# Main_8.net
KiCad netlist of a schematic drawn in Altium Designer
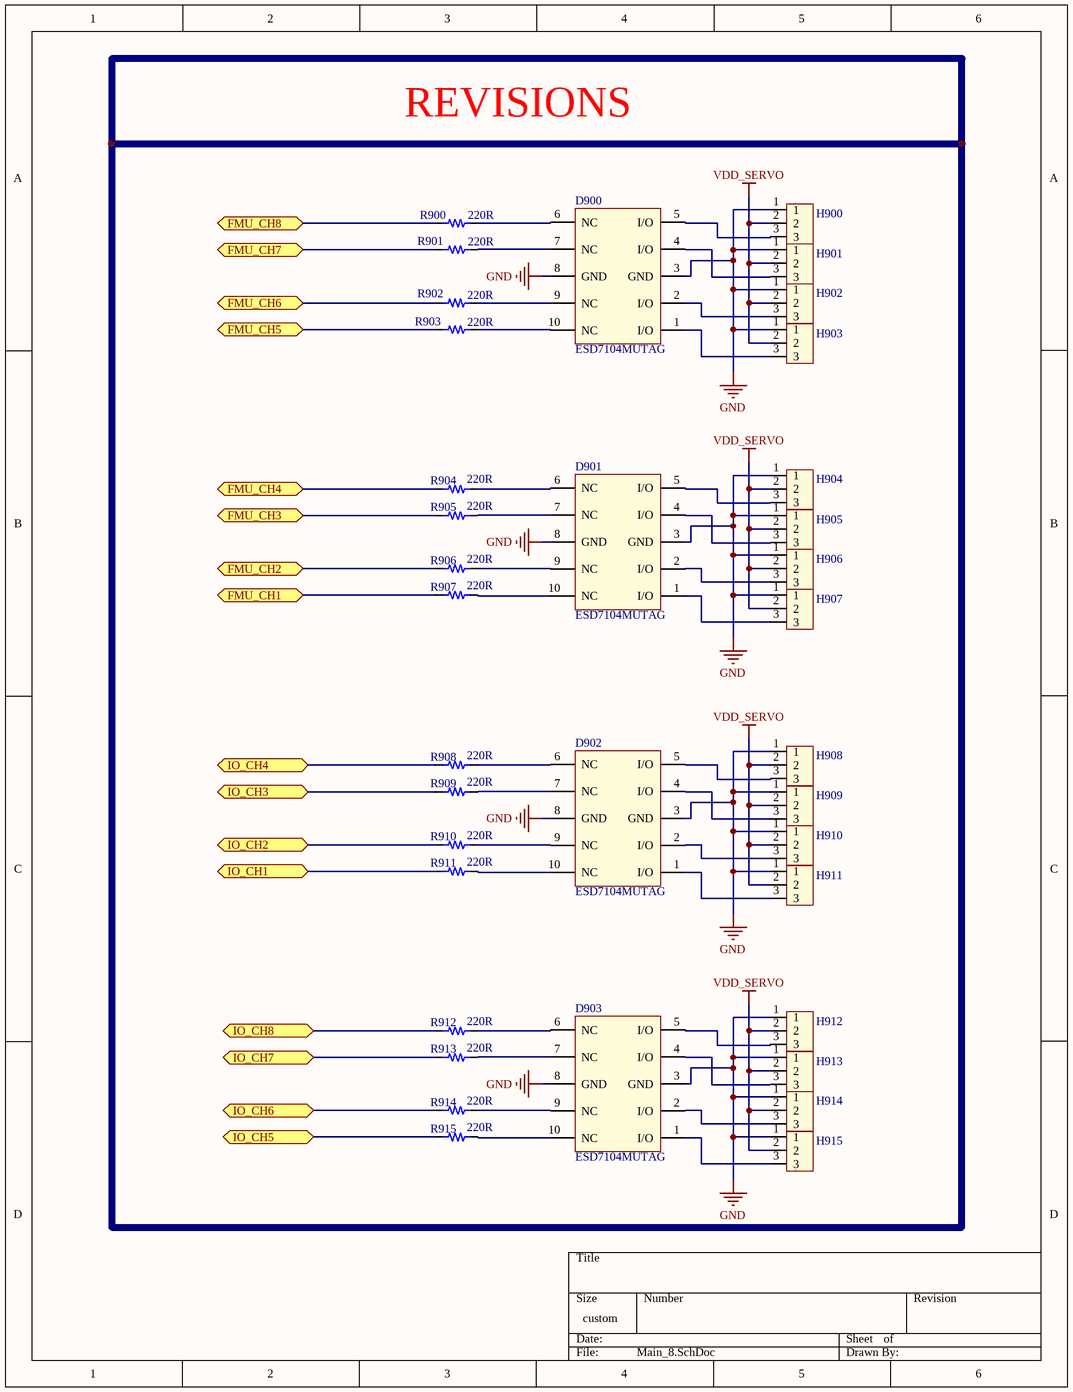
[diagram p0: Main_8.SchDoc]

(export (version "E")
  (design (tool "Eeschema 10.0.6"))
  (components
    (comp (ref "D900")
      (value "ESD7104MUTAG")
      (footprint "UDFN10 2.5x1, 0.5P")
      (description "TVS DIODE 5VWM 10VC 10UDFN")
      (libsource (lib "UAV_mainboard") (part "ESD7104MUTAG"))
    )
    (comp (ref "D901")
      (value "ESD7104MUTAG")
      (footprint "UDFN10 2.5x1, 0.5P")
      (description "TVS DIODE 5VWM 10VC 10UDFN")
      (libsource (lib "UAV_mainboard") (part "ESD7104MUTAG"))
    )
    (comp (ref "D902")
      (value "ESD7104MUTAG")
      (footprint "UDFN10 2.5x1, 0.5P")
      (description "TVS DIODE 5VWM 10VC 10UDFN")
      (libsource (lib "UAV_mainboard") (part "ESD7104MUTAG"))
    )
    (comp (ref "D903")
      (value "ESD7104MUTAG")
      (footprint "UDFN10 2.5x1, 0.5P")
      (description "TVS DIODE 5VWM 10VC 10UDFN")
      (libsource (lib "UAV_mainboard") (part "ESD7104MUTAG"))
    )
    (comp (ref "H900")
      (value "Header 3x1")
      (footprint "Header 3x1")
      (libsource (lib "UAV_mainboard") (part "Header 3x1"))
    )
    (comp (ref "H901")
      (value "Header 3x1")
      (footprint "Header 3x1")
      (libsource (lib "UAV_mainboard") (part "Header 3x1"))
    )
    (comp (ref "H902")
      (value "Header 3x1")
      (footprint "Header 3x1")
      (libsource (lib "UAV_mainboard") (part "Header 3x1"))
    )
    (comp (ref "H903")
      (value "Header 3x1")
      (footprint "Header 3x1")
      (libsource (lib "UAV_mainboard") (part "Header 3x1"))
    )
    (comp (ref "H904")
      (value "Header 3x1")
      (footprint "Header 3x1")
      (libsource (lib "UAV_mainboard") (part "Header 3x1"))
    )
    (comp (ref "H905")
      (value "Header 3x1")
      (footprint "Header 3x1")
      (libsource (lib "UAV_mainboard") (part "Header 3x1"))
    )
    (comp (ref "H906")
      (value "Header 3x1")
      (footprint "Header 3x1")
      (libsource (lib "UAV_mainboard") (part "Header 3x1"))
    )
    (comp (ref "H907")
      (value "Header 3x1")
      (footprint "Header 3x1")
      (libsource (lib "UAV_mainboard") (part "Header 3x1"))
    )
    (comp (ref "H908")
      (value "Header 3x1")
      (footprint "Header 3x1")
      (libsource (lib "UAV_mainboard") (part "Header 3x1"))
    )
    (comp (ref "H909")
      (value "Header 3x1")
      (footprint "Header 3x1")
      (libsource (lib "UAV_mainboard") (part "Header 3x1"))
    )
    (comp (ref "H910")
      (value "Header 3x1")
      (footprint "Header 3x1")
      (libsource (lib "UAV_mainboard") (part "Header 3x1"))
    )
    (comp (ref "H911")
      (value "Header 3x1")
      (footprint "Header 3x1")
      (libsource (lib "UAV_mainboard") (part "Header 3x1"))
    )
    (comp (ref "H912")
      (value "Header 3x1")
      (footprint "Header 3x1")
      (libsource (lib "UAV_mainboard") (part "Header 3x1"))
    )
    (comp (ref "H913")
      (value "Header 3x1")
      (footprint "Header 3x1")
      (libsource (lib "UAV_mainboard") (part "Header 3x1"))
    )
    (comp (ref "H914")
      (value "Header 3x1")
      (footprint "Header 3x1")
      (libsource (lib "UAV_mainboard") (part "Header 3x1"))
    )
    (comp (ref "H915")
      (value "Header 3x1")
      (footprint "Header 3x1")
      (libsource (lib "UAV_mainboard") (part "Header 3x1"))
    )
    (comp (ref "R900")
      (value "220R")
      (footprint "R0402")
      (description "RES 220 OHM 1% 1/16W 0402")
      (libsource (lib "UAV_mainboard") (part "RC0402FR-07220RL"))
    )
    (comp (ref "R901")
      (value "220R")
      (footprint "R0402")
      (description "RES 220 OHM 1% 1/16W 0402")
      (libsource (lib "UAV_mainboard") (part "RC0402FR-07220RL"))
    )
    (comp (ref "R902")
      (value "220R")
      (footprint "R0402")
      (description "RES 220 OHM 1% 1/16W 0402")
      (libsource (lib "UAV_mainboard") (part "RC0402FR-07220RL"))
    )
    (comp (ref "R903")
      (value "220R")
      (footprint "R0402")
      (description "RES 220 OHM 1% 1/16W 0402")
      (libsource (lib "UAV_mainboard") (part "RC0402FR-07220RL"))
    )
    (comp (ref "R904")
      (value "220R")
      (footprint "R0402")
      (description "RES 220 OHM 1% 1/16W 0402")
      (libsource (lib "UAV_mainboard") (part "RC0402FR-07220RL"))
    )
    (comp (ref "R905")
      (value "220R")
      (footprint "R0402")
      (description "RES 220 OHM 1% 1/16W 0402")
      (libsource (lib "UAV_mainboard") (part "RC0402FR-07220RL"))
    )
    (comp (ref "R906")
      (value "220R")
      (footprint "R0402")
      (description "RES 220 OHM 1% 1/16W 0402")
      (libsource (lib "UAV_mainboard") (part "RC0402FR-07220RL"))
    )
    (comp (ref "R907")
      (value "220R")
      (footprint "R0402")
      (description "RES 220 OHM 1% 1/16W 0402")
      (libsource (lib "UAV_mainboard") (part "RC0402FR-07220RL"))
    )
    (comp (ref "R908")
      (value "220R")
      (footprint "R0402")
      (description "RES 220 OHM 1% 1/16W 0402")
      (libsource (lib "UAV_mainboard") (part "RC0402FR-07220RL"))
    )
    (comp (ref "R909")
      (value "220R")
      (footprint "R0402")
      (description "RES 220 OHM 1% 1/16W 0402")
      (libsource (lib "UAV_mainboard") (part "RC0402FR-07220RL"))
    )
    (comp (ref "R910")
      (value "220R")
      (footprint "R0402")
      (description "RES 220 OHM 1% 1/16W 0402")
      (libsource (lib "UAV_mainboard") (part "RC0402FR-07220RL"))
    )
    (comp (ref "R911")
      (value "220R")
      (footprint "R0402")
      (description "RES 220 OHM 1% 1/16W 0402")
      (libsource (lib "UAV_mainboard") (part "RC0402FR-07220RL"))
    )
    (comp (ref "R912")
      (value "220R")
      (footprint "R0402")
      (description "RES 220 OHM 1% 1/16W 0402")
      (libsource (lib "UAV_mainboard") (part "RC0402FR-07220RL"))
    )
    (comp (ref "R913")
      (value "220R")
      (footprint "R0402")
      (description "RES 220 OHM 1% 1/16W 0402")
      (libsource (lib "UAV_mainboard") (part "RC0402FR-07220RL"))
    )
    (comp (ref "R914")
      (value "220R")
      (footprint "R0402")
      (description "RES 220 OHM 1% 1/16W 0402")
      (libsource (lib "UAV_mainboard") (part "RC0402FR-07220RL"))
    )
    (comp (ref "R915")
      (value "220R")
      (footprint "R0402")
      (description "RES 220 OHM 1% 1/16W 0402")
      (libsource (lib "UAV_mainboard") (part "RC0402FR-07220RL"))
    )
  )
  (nets
    (net (code "1") (name "/FMU_CH1") (class "Default")
      (node (ref "R907") (pin "1") (pinfunction "1_1") (pintype "passive"))
    )
    (net (code "2") (name "/FMU_CH2") (class "Default")
      (node (ref "R906") (pin "1") (pinfunction "1_1") (pintype "passive"))
    )
    (net (code "3") (name "/FMU_CH3") (class "Default")
      (node (ref "R905") (pin "1") (pinfunction "1_1") (pintype "passive"))
    )
    (net (code "4") (name "/FMU_CH4") (class "Default")
      (node (ref "R904") (pin "1") (pinfunction "1_1") (pintype "passive"))
    )
    (net (code "5") (name "/FMU_CH5") (class "Default")
      (node (ref "R903") (pin "1") (pinfunction "1_1") (pintype "passive"))
    )
    (net (code "6") (name "/FMU_CH6") (class "Default")
      (node (ref "R902") (pin "1") (pinfunction "1_1") (pintype "passive"))
    )
    (net (code "7") (name "/FMU_CH7") (class "Default")
      (node (ref "R901") (pin "1") (pinfunction "1_1") (pintype "passive"))
    )
    (net (code "8") (name "/FMU_CH8") (class "Default")
      (node (ref "R900") (pin "1") (pinfunction "1_1") (pintype "passive"))
    )
    (net (code "9") (name "/IO_CH1") (class "Default")
      (node (ref "R911") (pin "1") (pinfunction "1_1") (pintype "passive"))
    )
    (net (code "10") (name "/IO_CH2") (class "Default")
      (node (ref "R910") (pin "1") (pinfunction "1_1") (pintype "passive"))
    )
    (net (code "11") (name "/IO_CH3") (class "Default")
      (node (ref "R909") (pin "1") (pinfunction "1_1") (pintype "passive"))
    )
    (net (code "12") (name "/IO_CH4") (class "Default")
      (node (ref "R908") (pin "1") (pinfunction "1_1") (pintype "passive"))
    )
    (net (code "13") (name "/IO_CH5") (class "Default")
      (node (ref "R915") (pin "1") (pinfunction "1_1") (pintype "passive"))
    )
    (net (code "14") (name "/IO_CH6") (class "Default")
      (node (ref "R914") (pin "1") (pinfunction "1_1") (pintype "passive"))
    )
    (net (code "15") (name "/IO_CH7") (class "Default")
      (node (ref "R913") (pin "1") (pinfunction "1_1") (pintype "passive"))
    )
    (net (code "16") (name "/IO_CH8") (class "Default")
      (node (ref "R912") (pin "1") (pinfunction "1_1") (pintype "passive"))
    )
    (net (code "17") (name "GND") (class "Default")
      (node (ref "D900") (pin "3") (pinfunction "GND_3") (pintype "passive"))
      (node (ref "D900") (pin "8") (pinfunction "GND_8") (pintype "passive"))
      (node (ref "D901") (pin "3") (pinfunction "GND_3") (pintype "passive"))
      (node (ref "D901") (pin "8") (pinfunction "GND_8") (pintype "passive"))
      (node (ref "D902") (pin "3") (pinfunction "GND_3") (pintype "passive"))
      (node (ref "D902") (pin "8") (pinfunction "GND_8") (pintype "passive"))
      (node (ref "D903") (pin "3") (pinfunction "GND_3") (pintype "passive"))
      (node (ref "D903") (pin "8") (pinfunction "GND_8") (pintype "passive"))
      (node (ref "H900") (pin "1") (pinfunction "1_1") (pintype "passive"))
      (node (ref "H901") (pin "1") (pinfunction "1_1") (pintype "passive"))
      (node (ref "H902") (pin "1") (pinfunction "1_1") (pintype "passive"))
      (node (ref "H903") (pin "1") (pinfunction "1_1") (pintype "passive"))
      (node (ref "H904") (pin "1") (pinfunction "1_1") (pintype "passive"))
      (node (ref "H905") (pin "1") (pinfunction "1_1") (pintype "passive"))
      (node (ref "H906") (pin "1") (pinfunction "1_1") (pintype "passive"))
      (node (ref "H907") (pin "1") (pinfunction "1_1") (pintype "passive"))
      (node (ref "H908") (pin "1") (pinfunction "1_1") (pintype "passive"))
      (node (ref "H909") (pin "1") (pinfunction "1_1") (pintype "passive"))
      (node (ref "H910") (pin "1") (pinfunction "1_1") (pintype "passive"))
      (node (ref "H911") (pin "1") (pinfunction "1_1") (pintype "passive"))
      (node (ref "H912") (pin "1") (pinfunction "1_1") (pintype "passive"))
      (node (ref "H913") (pin "1") (pinfunction "1_1") (pintype "passive"))
      (node (ref "H914") (pin "1") (pinfunction "1_1") (pintype "passive"))
      (node (ref "H915") (pin "1") (pinfunction "1_1") (pintype "passive"))
    )
    (net (code "18") (name "Net-(D900-I{slash}O-Pad1)") (class "Default")
      (node (ref "D900") (pin "1") (pinfunction "I/O_1") (pintype "passive"))
      (node (ref "H903") (pin "3") (pinfunction "3_3") (pintype "passive"))
    )
    (net (code "19") (name "Net-(D900-I{slash}O-Pad2)") (class "Default")
      (node (ref "D900") (pin "2") (pinfunction "I/O_2") (pintype "passive"))
      (node (ref "H902") (pin "3") (pinfunction "3_3") (pintype "passive"))
    )
    (net (code "20") (name "Net-(D900-I{slash}O-Pad4)") (class "Default")
      (node (ref "D900") (pin "4") (pinfunction "I/O_4") (pintype "passive"))
      (node (ref "H901") (pin "3") (pinfunction "3_3") (pintype "passive"))
    )
    (net (code "21") (name "Net-(D900-I{slash}O-Pad5)") (class "Default")
      (node (ref "D900") (pin "5") (pinfunction "I/O_5") (pintype "passive"))
      (node (ref "H900") (pin "3") (pinfunction "3_3") (pintype "passive"))
    )
    (net (code "22") (name "Net-(D900-NC-Pad6)") (class "Default")
      (node (ref "D900") (pin "6") (pinfunction "NC_6") (pintype "passive"))
      (node (ref "R900") (pin "2") (pinfunction "2_2") (pintype "passive"))
    )
    (net (code "23") (name "Net-(D900-NC-Pad7)") (class "Default")
      (node (ref "D900") (pin "7") (pinfunction "NC_7") (pintype "passive"))
      (node (ref "R901") (pin "2") (pinfunction "2_2") (pintype "passive"))
    )
    (net (code "24") (name "Net-(D900-NC-Pad9)") (class "Default")
      (node (ref "D900") (pin "9") (pinfunction "NC_9") (pintype "passive"))
      (node (ref "R902") (pin "2") (pinfunction "2_2") (pintype "passive"))
    )
    (net (code "25") (name "Net-(D900-NC-Pad10)") (class "Default")
      (node (ref "D900") (pin "10") (pinfunction "NC_10") (pintype "passive"))
      (node (ref "R903") (pin "2") (pinfunction "2_2") (pintype "passive"))
    )
    (net (code "26") (name "Net-(D901-I{slash}O-Pad1)") (class "Default")
      (node (ref "D901") (pin "1") (pinfunction "I/O_1") (pintype "passive"))
      (node (ref "H907") (pin "3") (pinfunction "3_3") (pintype "passive"))
    )
    (net (code "27") (name "Net-(D901-I{slash}O-Pad2)") (class "Default")
      (node (ref "D901") (pin "2") (pinfunction "I/O_2") (pintype "passive"))
      (node (ref "H906") (pin "3") (pinfunction "3_3") (pintype "passive"))
    )
    (net (code "28") (name "Net-(D901-I{slash}O-Pad4)") (class "Default")
      (node (ref "D901") (pin "4") (pinfunction "I/O_4") (pintype "passive"))
      (node (ref "H905") (pin "3") (pinfunction "3_3") (pintype "passive"))
    )
    (net (code "29") (name "Net-(D901-I{slash}O-Pad5)") (class "Default")
      (node (ref "D901") (pin "5") (pinfunction "I/O_5") (pintype "passive"))
      (node (ref "H904") (pin "3") (pinfunction "3_3") (pintype "passive"))
    )
    (net (code "30") (name "Net-(D901-NC-Pad6)") (class "Default")
      (node (ref "D901") (pin "6") (pinfunction "NC_6") (pintype "passive"))
      (node (ref "R904") (pin "2") (pinfunction "2_2") (pintype "passive"))
    )
    (net (code "31") (name "Net-(D901-NC-Pad7)") (class "Default")
      (node (ref "D901") (pin "7") (pinfunction "NC_7") (pintype "passive"))
      (node (ref "R905") (pin "2") (pinfunction "2_2") (pintype "passive"))
    )
    (net (code "32") (name "Net-(D901-NC-Pad9)") (class "Default")
      (node (ref "D901") (pin "9") (pinfunction "NC_9") (pintype "passive"))
      (node (ref "R906") (pin "2") (pinfunction "2_2") (pintype "passive"))
    )
    (net (code "33") (name "Net-(D901-NC-Pad10)") (class "Default")
      (node (ref "D901") (pin "10") (pinfunction "NC_10") (pintype "passive"))
      (node (ref "R907") (pin "2") (pinfunction "2_2") (pintype "passive"))
    )
    (net (code "34") (name "Net-(D902-I{slash}O-Pad1)") (class "Default")
      (node (ref "D902") (pin "1") (pinfunction "I/O_1") (pintype "passive"))
      (node (ref "H911") (pin "3") (pinfunction "3_3") (pintype "passive"))
    )
    (net (code "35") (name "Net-(D902-I{slash}O-Pad2)") (class "Default")
      (node (ref "D902") (pin "2") (pinfunction "I/O_2") (pintype "passive"))
      (node (ref "H910") (pin "3") (pinfunction "3_3") (pintype "passive"))
    )
    (net (code "36") (name "Net-(D902-I{slash}O-Pad4)") (class "Default")
      (node (ref "D902") (pin "4") (pinfunction "I/O_4") (pintype "passive"))
      (node (ref "H909") (pin "3") (pinfunction "3_3") (pintype "passive"))
    )
    (net (code "37") (name "Net-(D902-I{slash}O-Pad5)") (class "Default")
      (node (ref "D902") (pin "5") (pinfunction "I/O_5") (pintype "passive"))
      (node (ref "H908") (pin "3") (pinfunction "3_3") (pintype "passive"))
    )
    (net (code "38") (name "Net-(D902-NC-Pad6)") (class "Default")
      (node (ref "D902") (pin "6") (pinfunction "NC_6") (pintype "passive"))
      (node (ref "R908") (pin "2") (pinfunction "2_2") (pintype "passive"))
    )
    (net (code "39") (name "Net-(D902-NC-Pad7)") (class "Default")
      (node (ref "D902") (pin "7") (pinfunction "NC_7") (pintype "passive"))
      (node (ref "R909") (pin "2") (pinfunction "2_2") (pintype "passive"))
    )
    (net (code "40") (name "Net-(D902-NC-Pad9)") (class "Default")
      (node (ref "D902") (pin "9") (pinfunction "NC_9") (pintype "passive"))
      (node (ref "R910") (pin "2") (pinfunction "2_2") (pintype "passive"))
    )
    (net (code "41") (name "Net-(D902-NC-Pad10)") (class "Default")
      (node (ref "D902") (pin "10") (pinfunction "NC_10") (pintype "passive"))
      (node (ref "R911") (pin "2") (pinfunction "2_2") (pintype "passive"))
    )
    (net (code "42") (name "Net-(D903-I{slash}O-Pad1)") (class "Default")
      (node (ref "D903") (pin "1") (pinfunction "I/O_1") (pintype "passive"))
      (node (ref "H915") (pin "3") (pinfunction "3_3") (pintype "passive"))
    )
    (net (code "43") (name "Net-(D903-I{slash}O-Pad2)") (class "Default")
      (node (ref "D903") (pin "2") (pinfunction "I/O_2") (pintype "passive"))
      (node (ref "H914") (pin "3") (pinfunction "3_3") (pintype "passive"))
    )
    (net (code "44") (name "Net-(D903-I{slash}O-Pad4)") (class "Default")
      (node (ref "D903") (pin "4") (pinfunction "I/O_4") (pintype "passive"))
      (node (ref "H913") (pin "3") (pinfunction "3_3") (pintype "passive"))
    )
    (net (code "45") (name "Net-(D903-I{slash}O-Pad5)") (class "Default")
      (node (ref "D903") (pin "5") (pinfunction "I/O_5") (pintype "passive"))
      (node (ref "H912") (pin "3") (pinfunction "3_3") (pintype "passive"))
    )
    (net (code "46") (name "Net-(D903-NC-Pad6)") (class "Default")
      (node (ref "D903") (pin "6") (pinfunction "NC_6") (pintype "passive"))
      (node (ref "R912") (pin "2") (pinfunction "2_2") (pintype "passive"))
    )
    (net (code "47") (name "Net-(D903-NC-Pad7)") (class "Default")
      (node (ref "D903") (pin "7") (pinfunction "NC_7") (pintype "passive"))
      (node (ref "R913") (pin "2") (pinfunction "2_2") (pintype "passive"))
    )
    (net (code "48") (name "Net-(D903-NC-Pad9)") (class "Default")
      (node (ref "D903") (pin "9") (pinfunction "NC_9") (pintype "passive"))
      (node (ref "R914") (pin "2") (pinfunction "2_2") (pintype "passive"))
    )
    (net (code "49") (name "Net-(D903-NC-Pad10)") (class "Default")
      (node (ref "D903") (pin "10") (pinfunction "NC_10") (pintype "passive"))
      (node (ref "R915") (pin "2") (pinfunction "2_2") (pintype "passive"))
    )
    (net (code "50") (name "VDD_SERVO") (class "Default")
      (node (ref "H900") (pin "2") (pinfunction "2_2") (pintype "passive"))
      (node (ref "H901") (pin "2") (pinfunction "2_2") (pintype "passive"))
      (node (ref "H902") (pin "2") (pinfunction "2_2") (pintype "passive"))
      (node (ref "H903") (pin "2") (pinfunction "2_2") (pintype "passive"))
      (node (ref "H904") (pin "2") (pinfunction "2_2") (pintype "passive"))
      (node (ref "H905") (pin "2") (pinfunction "2_2") (pintype "passive"))
      (node (ref "H906") (pin "2") (pinfunction "2_2") (pintype "passive"))
      (node (ref "H907") (pin "2") (pinfunction "2_2") (pintype "passive"))
      (node (ref "H908") (pin "2") (pinfunction "2_2") (pintype "passive"))
      (node (ref "H909") (pin "2") (pinfunction "2_2") (pintype "passive"))
      (node (ref "H910") (pin "2") (pinfunction "2_2") (pintype "passive"))
      (node (ref "H911") (pin "2") (pinfunction "2_2") (pintype "passive"))
      (node (ref "H912") (pin "2") (pinfunction "2_2") (pintype "passive"))
      (node (ref "H913") (pin "2") (pinfunction "2_2") (pintype "passive"))
      (node (ref "H914") (pin "2") (pinfunction "2_2") (pintype "passive"))
      (node (ref "H915") (pin "2") (pinfunction "2_2") (pintype "passive"))
    )
  )
)
